# OASIS-Board.net
KiCad netlist of a schematic drawn in EAGLE
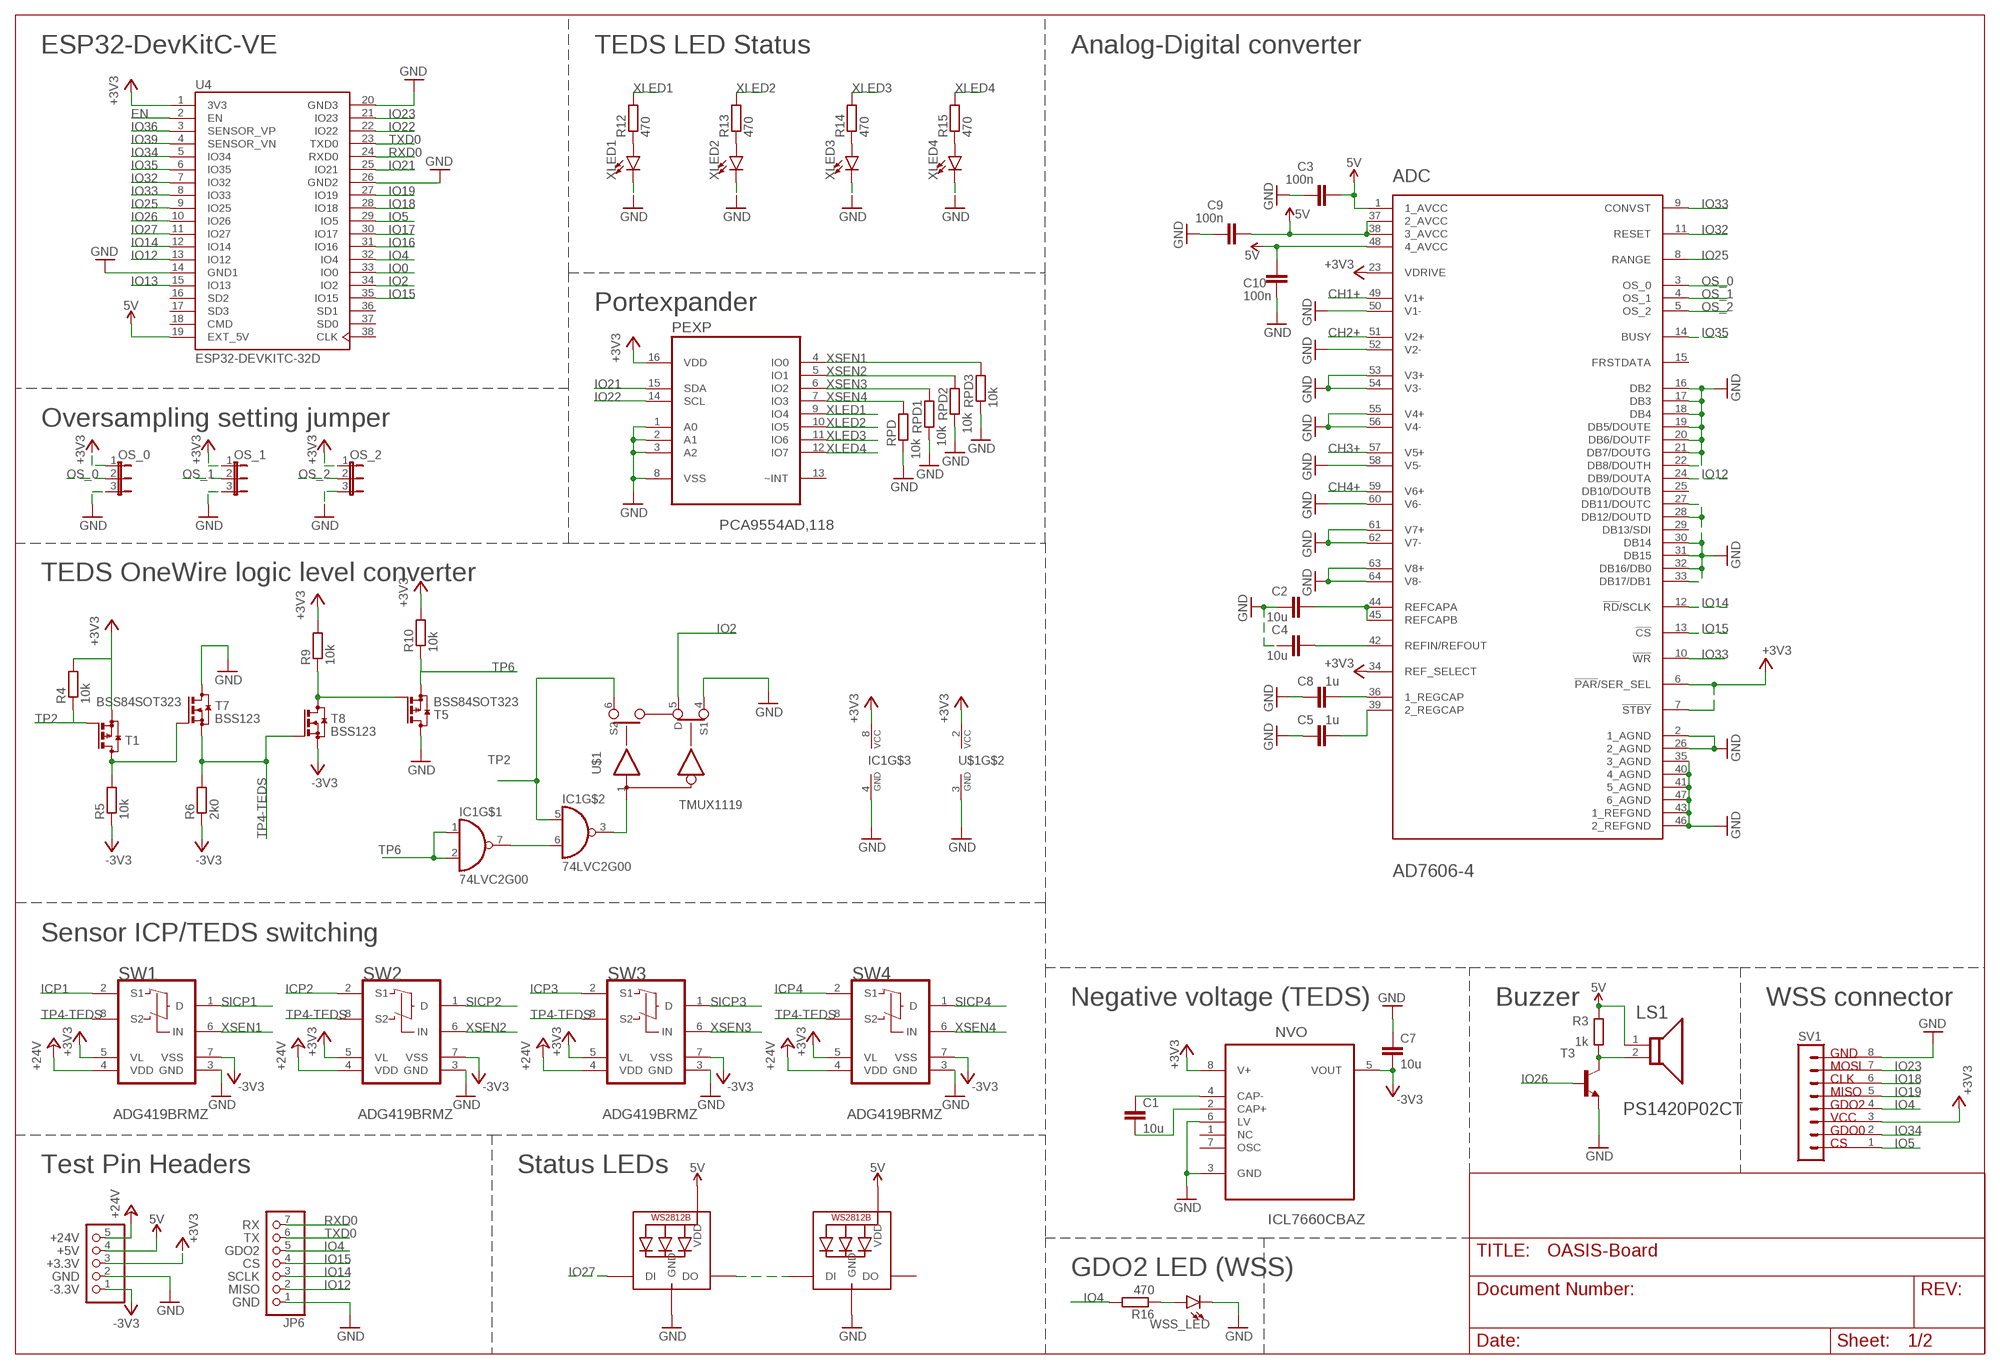
[diagram p0: schematic, sheet 1]
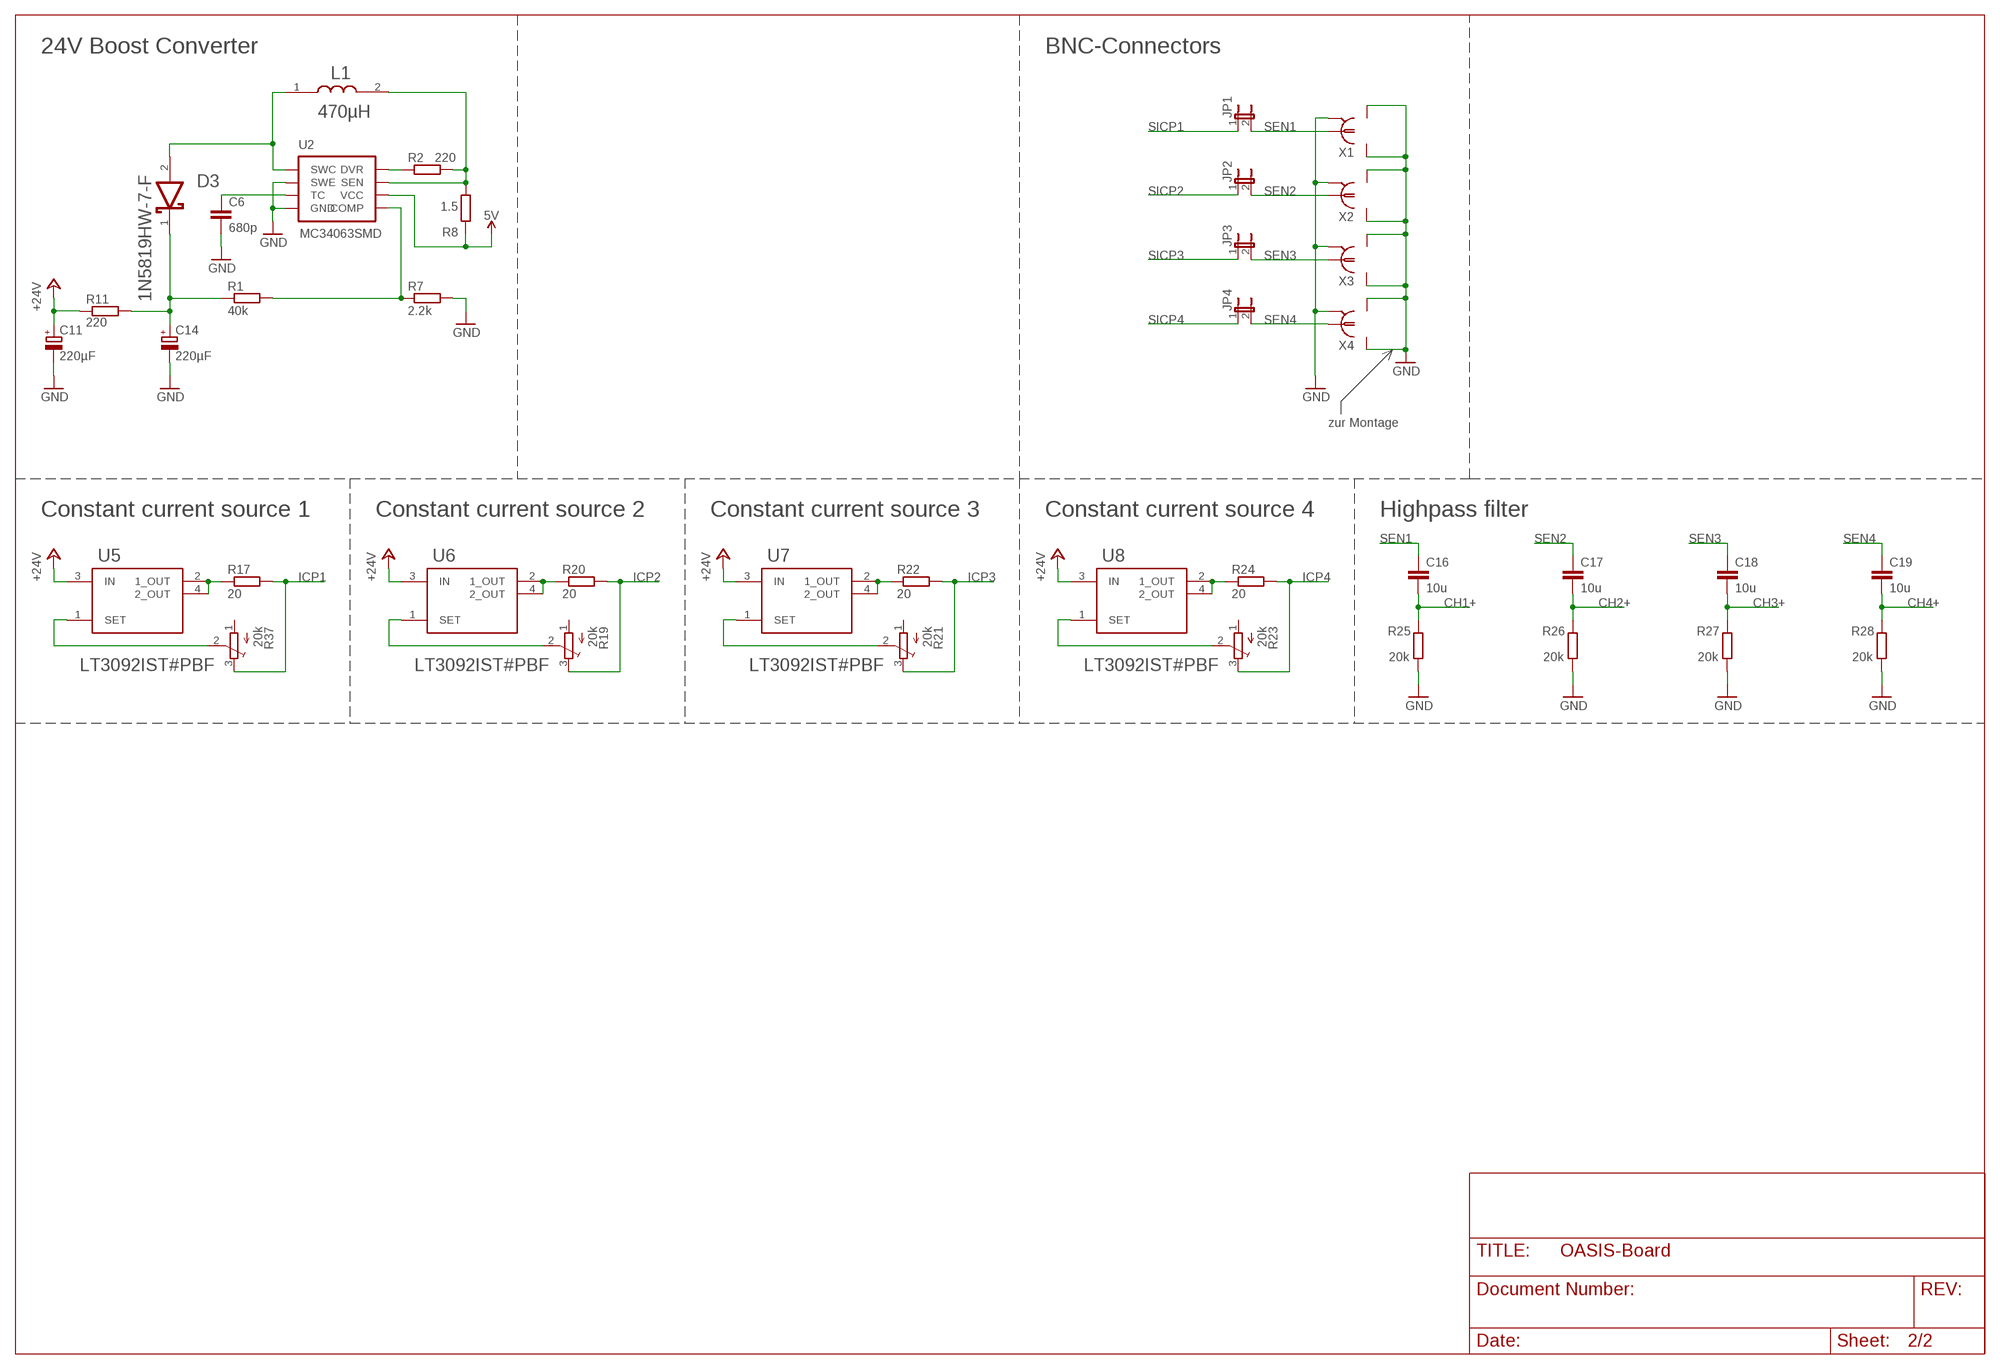
[diagram p1: schematic, sheet 2]

(export (version "E")
  (design (tool "Eeschema 10.0.6"))
  (components
    (comp (ref "ADC")
      (value "ANALOG_DEVICES_AD7606-4ANALOG_DEVICES_AD7606-4_0_0")
      (footprint "eagle-import:ANALOG_DEVICES_AD7606-4_0")
      (fields
        (field (name "DIGIKEY_PART_NUMBER") "505-AD7606-4-ND")
        (field (name "MF") "Analog Devices")
        (field (name "MOUSER_PART_NUMBER") "584-AD7606-4")
      )
      (libsource (lib "eagle-import") (part "ANALOG_DEVICES_AD7606-4ANALOG_DEVICES_AD7606-4_0_0"))
    )
    (comp (ref "C1")
      (value "10u")
      (footprint "eagle-import:C0603")
      (libsource (lib "eagle-import") (part "C-EUC0603"))
    )
    (comp (ref "C2")
      (value "10u")
      (footprint "eagle-import:C0603")
      (libsource (lib "eagle-import") (part "C-EUC0603"))
    )
    (comp (ref "C3")
      (value "100n")
      (footprint "eagle-import:C0603")
      (libsource (lib "eagle-import") (part "C-EUC0603"))
    )
    (comp (ref "C4")
      (value "10u")
      (footprint "eagle-import:C0603")
      (libsource (lib "eagle-import") (part "C-EUC0603"))
    )
    (comp (ref "C5")
      (value "1u")
      (footprint "eagle-import:C0603")
      (libsource (lib "eagle-import") (part "C-EUC0603"))
    )
    (comp (ref "C7")
      (value "10u")
      (footprint "eagle-import:C0603")
      (libsource (lib "eagle-import") (part "C-EUC0603"))
    )
    (comp (ref "C8")
      (value "1u")
      (footprint "eagle-import:C0603")
      (libsource (lib "eagle-import") (part "C-EUC0603"))
    )
    (comp (ref "C9")
      (value "100n")
      (footprint "eagle-import:C0603")
      (libsource (lib "eagle-import") (part "C-EUC0603"))
    )
    (comp (ref "C10")
      (value "100n")
      (footprint "eagle-import:C0603")
      (libsource (lib "eagle-import") (part "C-EUC0603"))
    )
    (comp (ref "IC1")
      (value "74LVC2G00")
      (footprint "eagle-import:TEXAS_INSTRUMENTS_SN74LVC2G00DCUT_2")
      (libsource (lib "eagle-import") (part "74LVC2G00"))
    )
    (comp (ref "JP5")
      (value "PINHD-1X5")
      (footprint "eagle-import:1X05")
      (libsource (lib "eagle-import") (part "PINHD-1X5"))
    )
    (comp (ref "JP6")
      (value "PINHD-1X7")
      (footprint "eagle-import:1X07")
      (libsource (lib "eagle-import") (part "PINHD-1X7"))
    )
    (comp (ref "LS1")
      (value "TDK_PS1420P02CTTDK_PS1420P02CT_0_0")
      (footprint "eagle-import:TDK_PS1420P02CT_0")
      (fields
        (field (name "DIGIKEY_PART_NUMBER") "445-2526-1-ND")
        (field (name "MF") "TDK")
        (field (name "MOUSER_PART_NUMBER") "810-PS1420P02CT")
      )
      (libsource (lib "eagle-import") (part "TDK_PS1420P02CTTDK_PS1420P02CT_0_0"))
    )
    (comp (ref "NVO")
      (value "ICL7660CBAZ")
      (footprint "eagle-import:SOIC127P600X175-8N")
      (fields (field (name "MF") "Renesas Electronics America Inc"))
      (libsource (lib "eagle-import") (part "ICL7660CBAZ"))
    )
    (comp (ref "OS_0")
      (value "JP2E")
      (footprint "eagle-import:JP2")
      (libsource (lib "eagle-import") (part "JP2E"))
    )
    (comp (ref "OS_1")
      (value "JP2E")
      (footprint "eagle-import:JP2")
      (libsource (lib "eagle-import") (part "JP2E"))
    )
    (comp (ref "OS_2")
      (value "JP2E")
      (footprint "eagle-import:JP2")
      (libsource (lib "eagle-import") (part "JP2E"))
    )
    (comp (ref "PEXP")
      (value "PCA9554AD,118")
      (footprint "eagle-import:SOIC127P1032X265-16N")
      (fields (field (name "MF") "NXP Semiconductors"))
      (libsource (lib "eagle-import") (part "PCA9554AD,118"))
    )
    (comp (ref "R3")
      (value "1k")
      (footprint "eagle-import:R0603")
      (libsource (lib "eagle-import") (part "rcl_334_R-EU_R0603"))
    )
    (comp (ref "R4")
      (value "10k")
      (footprint "eagle-import:R0603_MAYR")
      (libsource (lib "eagle-import") (part "R-EU_R0603_MAYR"))
    )
    (comp (ref "R5")
      (value "10k")
      (footprint "eagle-import:R0603_MAYR")
      (libsource (lib "eagle-import") (part "R-EU_R0603_MAYR"))
    )
    (comp (ref "R6")
      (value "2k0")
      (footprint "eagle-import:R0603_MAYR")
      (libsource (lib "eagle-import") (part "R-EU_R0603_MAYR"))
    )
    (comp (ref "R9")
      (value "10k")
      (footprint "eagle-import:R0603_MAYR")
      (libsource (lib "eagle-import") (part "R-EU_R0603_MAYR"))
    )
    (comp (ref "R10")
      (value "10k")
      (footprint "eagle-import:R0603_MAYR")
      (libsource (lib "eagle-import") (part "R-EU_R0603_MAYR"))
    )
    (comp (ref "R12")
      (value "470")
      (footprint "eagle-import:R0603")
      (libsource (lib "eagle-import") (part "rcl_334_R-EU_R0603"))
    )
    (comp (ref "R13")
      (value "470")
      (footprint "eagle-import:R0603")
      (libsource (lib "eagle-import") (part "rcl_334_R-EU_R0603"))
    )
    (comp (ref "R14")
      (value "470")
      (footprint "eagle-import:R0603")
      (libsource (lib "eagle-import") (part "rcl_334_R-EU_R0603"))
    )
    (comp (ref "R15")
      (value "470")
      (footprint "eagle-import:R0603")
      (libsource (lib "eagle-import") (part "rcl_334_R-EU_R0603"))
    )
    (comp (ref "R16")
      (value "470")
      (footprint "eagle-import:R0603")
      (libsource (lib "eagle-import") (part "rcl_334_R-EU_R0603"))
    )
    (comp (ref "RPD")
      (value "10k")
      (footprint "eagle-import:R0603")
      (libsource (lib "eagle-import") (part "rcl_334_R-EU_R0603"))
    )
    (comp (ref "RPD1")
      (value "10k")
      (footprint "eagle-import:R0603")
      (libsource (lib "eagle-import") (part "rcl_334_R-EU_R0603"))
    )
    (comp (ref "RPD2")
      (value "10k")
      (footprint "eagle-import:R0603")
      (libsource (lib "eagle-import") (part "rcl_334_R-EU_R0603"))
    )
    (comp (ref "RPD3")
      (value "10k")
      (footprint "eagle-import:R0603")
      (libsource (lib "eagle-import") (part "rcl_334_R-EU_R0603"))
    )
    (comp (ref "STATUS")
      (value "WS2812B5050")
      (footprint "eagle-import:WS2812B")
      (fields (field (name "MF") "Worldsemi") (field (name "MP") "WS2812B"))
      (libsource (lib "eagle-import") (part "WS2812B5050"))
    )
    (comp (ref "SV1")
      (value "MA08-1")
      (footprint "eagle-import:MA08-1")
      (libsource (lib "eagle-import") (part "MA08-1"))
    )
    (comp (ref "SW1")
      (value "ANALOG_DEVICES_ADG419BRMZANALOG_DEVICES_ADG419BRMZ_0_0")
      (footprint "eagle-import:ANALOG_DEVICES_ADG419BRMZ_0")
      (fields (field (name "MF") "Analog Devices") (field (name "MPN") "ADG419BRMZ"))
      (libsource (lib "eagle-import") (part "ANALOG_DEVICES_ADG419BRMZANALOG_DEVICES_ADG419BRMZ_0_0"))
    )
    (comp (ref "SW2")
      (value "ANALOG_DEVICES_ADG419BRMZANALOG_DEVICES_ADG419BRMZ_0_0")
      (footprint "eagle-import:ANALOG_DEVICES_ADG419BRMZ_0")
      (fields (field (name "MF") "Analog Devices") (field (name "MPN") "ADG419BRMZ"))
      (libsource (lib "eagle-import") (part "ANALOG_DEVICES_ADG419BRMZANALOG_DEVICES_ADG419BRMZ_0_0"))
    )
    (comp (ref "SW3")
      (value "ANALOG_DEVICES_ADG419BRMZANALOG_DEVICES_ADG419BRMZ_0_0")
      (footprint "eagle-import:ANALOG_DEVICES_ADG419BRMZ_0")
      (fields (field (name "MF") "Analog Devices") (field (name "MPN") "ADG419BRMZ"))
      (libsource (lib "eagle-import") (part "ANALOG_DEVICES_ADG419BRMZANALOG_DEVICES_ADG419BRMZ_0_0"))
    )
    (comp (ref "SW4")
      (value "ANALOG_DEVICES_ADG419BRMZANALOG_DEVICES_ADG419BRMZ_0_0")
      (footprint "eagle-import:ANALOG_DEVICES_ADG419BRMZ_0")
      (fields (field (name "MF") "Analog Devices") (field (name "MPN") "ADG419BRMZ"))
      (libsource (lib "eagle-import") (part "ANALOG_DEVICES_ADG419BRMZANALOG_DEVICES_ADG419BRMZ_0_0"))
    )
    (comp (ref "T1")
      (value "BSS84SOT323")
      (footprint "eagle-import:SOT323")
      (libsource (lib "eagle-import") (part "BSS84SOT323"))
    )
    (comp (ref "T3")
      (value "BCF32-NPN-SOT23-BEC")
      (footprint "eagle-import:SOT23-BEC")
      (libsource (lib "eagle-import") (part "-NPN-SOT23-BECBCF32"))
    )
    (comp (ref "T5")
      (value "BSS84SOT323")
      (footprint "eagle-import:SOT323")
      (libsource (lib "eagle-import") (part "BSS84SOT323"))
    )
    (comp (ref "T7")
      (value "BSS123")
      (footprint "eagle-import:SOT23")
      (libsource (lib "eagle-import") (part "BSS123"))
    )
    (comp (ref "T8")
      (value "BSS123")
      (footprint "eagle-import:SOT23")
      (libsource (lib "eagle-import") (part "BSS123"))
    )
    (comp (ref "U$1")
      (value "TMUX1119")
      (footprint "eagle-import:TEXAS_INSTRUMENTS_TMUX1119DCKR_3")
      (libsource (lib "eagle-import") (part "TMUX1119"))
    )
    (comp (ref "U4")
      (value "ESP32-DEVKITC-32D")
      (footprint "eagle-import:MODULE_ESP32-DEVKITC-32D")
      (fields (field (name "MF") "Espressif Systems"))
      (libsource (lib "eagle-import") (part "ESP32-DEVKITC-32D"))
    )
    (comp (ref "WLAN")
      (value "WS2812B5050")
      (footprint "eagle-import:WS2812B")
      (fields (field (name "MF") "Worldsemi") (field (name "MP") "WS2812B"))
      (libsource (lib "eagle-import") (part "WS2812B5050"))
    )
    (comp (ref "WSS_LED")
      (value "LED0603")
      (footprint "eagle-import:LED-0603")
      (libsource (lib "eagle-import") (part "LED0603"))
    )
    (comp (ref "XLED1")
      (value "LED0603")
      (footprint "eagle-import:LED-0603")
      (libsource (lib "eagle-import") (part "LED0603"))
    )
    (comp (ref "XLED2")
      (value "LED0603")
      (footprint "eagle-import:LED-0603")
      (libsource (lib "eagle-import") (part "LED0603"))
    )
    (comp (ref "XLED3")
      (value "LED0603")
      (footprint "eagle-import:LED-0603")
      (libsource (lib "eagle-import") (part "LED0603"))
    )
    (comp (ref "XLED4")
      (value "LED0603")
      (footprint "eagle-import:LED-0603")
      (libsource (lib "eagle-import") (part "LED0603"))
    )
    (comp (ref "C6")
      (value "680p")
      (footprint "eagle-import:C0603")
      (libsource (lib "eagle-import") (part "C-EUC0603"))
    )
    (comp (ref "C11")
      (value "220µF")
      (footprint "eagle-import:153CLV-1012")
      (libsource (lib "eagle-import") (part "CPOL-EU153CLV-1012"))
    )
    (comp (ref "C14")
      (value "220µF")
      (footprint "eagle-import:153CLV-1012")
      (libsource (lib "eagle-import") (part "CPOL-EU153CLV-1012"))
    )
    (comp (ref "C16")
      (value "10u")
      (footprint "eagle-import:C0603")
      (libsource (lib "eagle-import") (part "C-EUC0603"))
    )
    (comp (ref "C17")
      (value "10u")
      (footprint "eagle-import:C0603")
      (libsource (lib "eagle-import") (part "C-EUC0603"))
    )
    (comp (ref "C18")
      (value "10u")
      (footprint "eagle-import:C0603")
      (libsource (lib "eagle-import") (part "C-EUC0603"))
    )
    (comp (ref "C19")
      (value "10u")
      (footprint "eagle-import:C0603")
      (libsource (lib "eagle-import") (part "C-EUC0603"))
    )
    (comp (ref "D3")
      (value "DIODES_1N5819HW-7-FDIODES_1N5819HW-7-F_0_1")
      (footprint "eagle-import:DIODES_1N5819HW-7-F_1")
      (fields
        (field (name "DIGIKEY_PART_NUMBER") "1N5819HW-FDICT-ND")
        (field (name "MF") "Diodes")
        (field (name "MOUSER_PART_NUMBER") "621-1N5819HW-F")
      )
      (libsource (lib "eagle-import") (part "DIODES_1N5819HW-7-FDIODES_1N5819HW-7-F_0_1"))
    )
    (comp (ref "JP1")
      (value "JP1E")
      (footprint "eagle-import:JP1")
      (libsource (lib "eagle-import") (part "JP1E"))
    )
    (comp (ref "JP2")
      (value "JP1E")
      (footprint "eagle-import:JP1")
      (libsource (lib "eagle-import") (part "JP1E"))
    )
    (comp (ref "JP3")
      (value "JP1E")
      (footprint "eagle-import:JP1")
      (libsource (lib "eagle-import") (part "JP1E"))
    )
    (comp (ref "JP4")
      (value "JP1E")
      (footprint "eagle-import:JP1")
      (libsource (lib "eagle-import") (part "JP1E"))
    )
    (comp (ref "L1")
      (value "BOURNS_SRR1260-470MBOURNS_SRR1260-470M_0_0")
      (footprint "eagle-import:BOURNS_SRR1260-470M_0")
      (fields
        (field (name "DIGIKEY_PART_NUMBER") "SRR1260-470MCT-ND")
        (field (name "MF") "Bourns")
        (field (name "MOUSER_PART_NUMBER") "652-SRR1260-470M")
      )
      (libsource (lib "eagle-import") (part "BOURNS_SRR1260-470MBOURNS_SRR1260-470M_0_0"))
    )
    (comp (ref "R1")
      (value "40k")
      (footprint "eagle-import:R0603")
      (libsource (lib "eagle-import") (part "rcl_334_R-EU_R0603"))
    )
    (comp (ref "R2")
      (value "220")
      (footprint "eagle-import:R0603")
      (libsource (lib "eagle-import") (part "rcl_334_R-EU_R0603"))
    )
    (comp (ref "R7")
      (value "2.2k")
      (footprint "eagle-import:R0603")
      (libsource (lib "eagle-import") (part "rcl_334_R-EU_R0603"))
    )
    (comp (ref "R8")
      (value "1.5")
      (footprint "eagle-import:R0603")
      (libsource (lib "eagle-import") (part "rcl_334_R-EU_R0603"))
    )
    (comp (ref "R11")
      (value "220")
      (footprint "eagle-import:R0603")
      (libsource (lib "eagle-import") (part "rcl_334_R-EU_R0603"))
    )
    (comp (ref "R17")
      (value "20")
      (footprint "eagle-import:R0603")
      (libsource (lib "eagle-import") (part "rcl_334_R-EU_R0603"))
    )
    (comp (ref "R19")
      (value "20k")
      (footprint "eagle-import:SM-42_43W")
      (libsource (lib "eagle-import") (part "TRIM_EU-SM-42/43W"))
    )
    (comp (ref "R20")
      (value "20")
      (footprint "eagle-import:R0603")
      (libsource (lib "eagle-import") (part "rcl_334_R-EU_R0603"))
    )
    (comp (ref "R21")
      (value "20k")
      (footprint "eagle-import:SM-42_43W")
      (libsource (lib "eagle-import") (part "TRIM_EU-SM-42/43W"))
    )
    (comp (ref "R22")
      (value "20")
      (footprint "eagle-import:R0603")
      (libsource (lib "eagle-import") (part "rcl_334_R-EU_R0603"))
    )
    (comp (ref "R23")
      (value "20k")
      (footprint "eagle-import:SM-42_43W")
      (libsource (lib "eagle-import") (part "TRIM_EU-SM-42/43W"))
    )
    (comp (ref "R24")
      (value "20")
      (footprint "eagle-import:R0603")
      (libsource (lib "eagle-import") (part "rcl_334_R-EU_R0603"))
    )
    (comp (ref "R25")
      (value "20k")
      (footprint "eagle-import:R0603")
      (libsource (lib "eagle-import") (part "rcl_334_R-EU_R0603"))
    )
    (comp (ref "R26")
      (value "20k")
      (footprint "eagle-import:R0603")
      (libsource (lib "eagle-import") (part "rcl_334_R-EU_R0603"))
    )
    (comp (ref "R27")
      (value "20k")
      (footprint "eagle-import:R0603")
      (libsource (lib "eagle-import") (part "rcl_334_R-EU_R0603"))
    )
    (comp (ref "R28")
      (value "20k")
      (footprint "eagle-import:R0603")
      (libsource (lib "eagle-import") (part "rcl_334_R-EU_R0603"))
    )
    (comp (ref "R37")
      (value "20k")
      (footprint "eagle-import:SM-42_43W")
      (libsource (lib "eagle-import") (part "TRIM_EU-SM-42/43W"))
    )
    (comp (ref "U2")
      (value "MC34063SMD")
      (footprint "eagle-import:SO08")
      (libsource (lib "eagle-import") (part "MC34063SMD"))
    )
    (comp (ref "U5")
      (value "ANALOG_DEVICES_INC_LT3092IST#PBFANALOG_DEVICES_INC_LT3092IST#PBF_0_0")
      (footprint "eagle-import:ANALOG_DEVICES_INC_LT3092IST#PBF_0")
      (fields
        (field (name "DIGIKEY_PART_NUMBER") "LT3092IST#PBF-ND")
        (field (name "MF") "Analog Devices Inc")
        (field (name "MOUSER_PART_NUMBER") "584-LT3092IST#PBF")
      )
      (libsource (lib "eagle-import") (part "ANALOG_DEVICES_INC_LT3092IST#PBFANALOG_DEVICES_INC_LT3092IST#PBF_0_0"))
    )
    (comp (ref "U6")
      (value "ANALOG_DEVICES_INC_LT3092IST#PBFANALOG_DEVICES_INC_LT3092IST#PBF_0_0")
      (footprint "eagle-import:ANALOG_DEVICES_INC_LT3092IST#PBF_0")
      (fields
        (field (name "DIGIKEY_PART_NUMBER") "LT3092IST#PBF-ND")
        (field (name "MF") "Analog Devices Inc")
        (field (name "MOUSER_PART_NUMBER") "584-LT3092IST#PBF")
      )
      (libsource (lib "eagle-import") (part "ANALOG_DEVICES_INC_LT3092IST#PBFANALOG_DEVICES_INC_LT3092IST#PBF_0_0"))
    )
    (comp (ref "U7")
      (value "ANALOG_DEVICES_INC_LT3092IST#PBFANALOG_DEVICES_INC_LT3092IST#PBF_0_0")
      (footprint "eagle-import:ANALOG_DEVICES_INC_LT3092IST#PBF_0")
      (fields
        (field (name "DIGIKEY_PART_NUMBER") "LT3092IST#PBF-ND")
        (field (name "MF") "Analog Devices Inc")
        (field (name "MOUSER_PART_NUMBER") "584-LT3092IST#PBF")
      )
      (libsource (lib "eagle-import") (part "ANALOG_DEVICES_INC_LT3092IST#PBFANALOG_DEVICES_INC_LT3092IST#PBF_0_0"))
    )
    (comp (ref "U8")
      (value "ANALOG_DEVICES_INC_LT3092IST#PBFANALOG_DEVICES_INC_LT3092IST#PBF_0_0")
      (footprint "eagle-import:ANALOG_DEVICES_INC_LT3092IST#PBF_0")
      (fields
        (field (name "DIGIKEY_PART_NUMBER") "LT3092IST#PBF-ND")
        (field (name "MF") "Analog Devices Inc")
        (field (name "MOUSER_PART_NUMBER") "584-LT3092IST#PBF")
      )
      (libsource (lib "eagle-import") (part "ANALOG_DEVICES_INC_LT3092IST#PBFANALOG_DEVICES_INC_LT3092IST#PBF_0_0"))
    )
    (comp (ref "X1")
      (value "BNC")
      (footprint "eagle-import:AMP_227161")
      (libsource (lib "eagle-import") (part "BNC"))
    )
    (comp (ref "X2")
      (value "BNC")
      (footprint "eagle-import:AMP_227161")
      (libsource (lib "eagle-import") (part "BNC"))
    )
    (comp (ref "X3")
      (value "BNC")
      (footprint "eagle-import:AMP_227161")
      (libsource (lib "eagle-import") (part "BNC"))
    )
    (comp (ref "X4")
      (value "BNC")
      (footprint "eagle-import:AMP_227161")
      (libsource (lib "eagle-import") (part "BNC"))
    )
  )
  (nets
    (net (code "1") (name "+3V3") (class "Default")
      (node (ref "ADC") (pin "23") (pinfunction "VDRIVE_23") (pintype "power_in"))
      (node (ref "ADC") (pin "34") (pinfunction "REF_SELECT_34") (pintype "input"))
      (node (ref "ADC") (pin "6") (pinfunction "~{PAR}/SER_SEL_6") (pintype "input"))
      (node (ref "ADC") (pin "7") (pinfunction "~{STBY}_7") (pintype "input"))
      (node (ref "IC1") (pin "8") (pinfunction "VCC_8") (pintype "power_in"))
      (node (ref "JP5") (pin "3") (pinfunction "3_3") (pintype "passive"))
      (node (ref "NVO") (pin "8") (pinfunction "V+_8") (pintype "power_in"))
      (node (ref "OS_0") (pin "1") (pinfunction "1_1") (pintype "passive"))
      (node (ref "OS_1") (pin "1") (pinfunction "1_1") (pintype "passive"))
      (node (ref "OS_2") (pin "1") (pinfunction "1_1") (pintype "passive"))
      (node (ref "PEXP") (pin "16") (pinfunction "VDD_16") (pintype "power_in"))
      (node (ref "R10") (pin "2") (pinfunction "2_2") (pintype "passive"))
      (node (ref "R4") (pin "2") (pinfunction "2_2") (pintype "passive"))
      (node (ref "R9") (pin "2") (pinfunction "2_2") (pintype "passive"))
      (node (ref "SV1") (pin "3") (pinfunction "3_3") (pintype "passive"))
      (node (ref "SW1") (pin "5") (pinfunction "VL_5") (pintype "power_in"))
      (node (ref "SW2") (pin "5") (pinfunction "VL_5") (pintype "power_in"))
      (node (ref "SW3") (pin "5") (pinfunction "VL_5") (pintype "power_in"))
      (node (ref "SW4") (pin "5") (pinfunction "VL_5") (pintype "power_in"))
      (node (ref "T1") (pin "3") (pinfunction "S_3") (pintype "passive"))
      (node (ref "U$1") (pin "2") (pinfunction "VCC_2") (pintype "power_in"))
      (node (ref "U4") (pin "1") (pinfunction "3V3_1") (pintype "power_in"))
    )
    (net (code "2") (name "+24V") (class "Default")
      (node (ref "C11") (pin "+") (pinfunction "+_+") (pintype "passive"))
      (node (ref "JP5") (pin "5") (pinfunction "5_5") (pintype "passive"))
      (node (ref "R11") (pin "1") (pinfunction "1_1") (pintype "passive"))
      (node (ref "SW1") (pin "4") (pinfunction "VDD_4") (pintype "power_in"))
      (node (ref "SW2") (pin "4") (pinfunction "VDD_4") (pintype "power_in"))
      (node (ref "SW3") (pin "4") (pinfunction "VDD_4") (pintype "power_in"))
      (node (ref "SW4") (pin "4") (pinfunction "VDD_4") (pintype "power_in"))
      (node (ref "U5") (pin "3") (pinfunction "IN_3") (pintype "input"))
      (node (ref "U6") (pin "3") (pinfunction "IN_3") (pintype "input"))
      (node (ref "U7") (pin "3") (pinfunction "IN_3") (pintype "input"))
      (node (ref "U8") (pin "3") (pinfunction "IN_3") (pintype "input"))
    )
    (net (code "3") (name "5V") (class "Default")
      (node (ref "ADC") (pin "1") (pinfunction "1_AVCC_1") (pintype "power_in"))
      (node (ref "ADC") (pin "37") (pinfunction "2_AVCC_37") (pintype "power_in"))
      (node (ref "ADC") (pin "38") (pinfunction "3_AVCC_38") (pintype "power_in"))
      (node (ref "ADC") (pin "48") (pinfunction "4_AVCC_48") (pintype "power_in"))
      (node (ref "C10") (pin "2") (pinfunction "2_2") (pintype "passive"))
      (node (ref "C3") (pin "2") (pinfunction "2_2") (pintype "passive"))
      (node (ref "C9") (pin "2") (pinfunction "2_2") (pintype "passive"))
      (node (ref "JP5") (pin "4") (pinfunction "4_4") (pintype "passive"))
      (node (ref "LS1") (pin "1") (pinfunction "1_1") (pintype "bidirectional"))
      (node (ref "R3") (pin "2") (pinfunction "2_2") (pintype "passive"))
      (node (ref "R8") (pin "1") (pinfunction "1_1") (pintype "passive"))
      (node (ref "STATUS") (pin "1-VDD") (pinfunction "VDD_1-VDD") (pintype "power_in"))
      (node (ref "U2") (pin "6") (pinfunction "VCC_6") (pintype "bidirectional"))
      (node (ref "U4") (pin "19") (pinfunction "EXT_5V_19") (pintype "power_in"))
      (node (ref "WLAN") (pin "1-VDD") (pinfunction "VDD_1-VDD") (pintype "power_in"))
    )
    (net (code "4") (name "CH1+") (class "Default")
      (node (ref "ADC") (pin "49") (pinfunction "V1+_49") (pintype "passive"))
      (node (ref "C16") (pin "2") (pinfunction "2_2") (pintype "passive"))
      (node (ref "R25") (pin "2") (pinfunction "2_2") (pintype "passive"))
    )
    (net (code "5") (name "CH2+") (class "Default")
      (node (ref "ADC") (pin "51") (pinfunction "V2+_51") (pintype "passive"))
      (node (ref "C17") (pin "2") (pinfunction "2_2") (pintype "passive"))
      (node (ref "R26") (pin "2") (pinfunction "2_2") (pintype "passive"))
    )
    (net (code "6") (name "CH3+") (class "Default")
      (node (ref "ADC") (pin "57") (pinfunction "V5+_57") (pintype "passive"))
      (node (ref "C18") (pin "2") (pinfunction "2_2") (pintype "passive"))
      (node (ref "R27") (pin "2") (pinfunction "2_2") (pintype "passive"))
    )
    (net (code "7") (name "CH4+") (class "Default")
      (node (ref "ADC") (pin "59") (pinfunction "V6+_59") (pintype "passive"))
      (node (ref "C19") (pin "2") (pinfunction "2_2") (pintype "passive"))
      (node (ref "R28") (pin "2") (pinfunction "2_2") (pintype "passive"))
    )
    (net (code "8") (name "EN") (class "Default")
      (node (ref "U4") (pin "2") (pinfunction "EN_2") (pintype "input"))
    )
    (net (code "9") (name "GND") (class "Default")
      (node (ref "ADC") (pin "16") (pinfunction "DB2_16") (pintype "bidirectional"))
      (node (ref "ADC") (pin "17") (pinfunction "DB3_17") (pintype "bidirectional"))
      (node (ref "ADC") (pin "18") (pinfunction "DB4_18") (pintype "bidirectional"))
      (node (ref "ADC") (pin "19") (pinfunction "DB5/DOUTE_19") (pintype "bidirectional"))
      (node (ref "ADC") (pin "2") (pinfunction "1_AGND_2") (pintype "power_in"))
      (node (ref "ADC") (pin "20") (pinfunction "DB6/DOUTF_20") (pintype "bidirectional"))
      (node (ref "ADC") (pin "21") (pinfunction "DB7/DOUTG_21") (pintype "bidirectional"))
      (node (ref "ADC") (pin "22") (pinfunction "DB8/DOUTH_22") (pintype "bidirectional"))
      (node (ref "ADC") (pin "26") (pinfunction "2_AGND_26") (pintype "power_in"))
      (node (ref "ADC") (pin "27") (pinfunction "DB11/DOUTC_27") (pintype "bidirectional"))
      (node (ref "ADC") (pin "28") (pinfunction "DB12/DOUTD_28") (pintype "bidirectional"))
      (node (ref "ADC") (pin "30") (pinfunction "DB14_30") (pintype "bidirectional"))
      (node (ref "ADC") (pin "31") (pinfunction "DB15_31") (pintype "bidirectional"))
      (node (ref "ADC") (pin "32") (pinfunction "DB16/DB0_32") (pintype "bidirectional"))
      (node (ref "ADC") (pin "33") (pinfunction "DB17/DB1_33") (pintype "bidirectional"))
      (node (ref "ADC") (pin "35") (pinfunction "3_AGND_35") (pintype "power_in"))
      (node (ref "ADC") (pin "40") (pinfunction "4_AGND_40") (pintype "power_in"))
      (node (ref "ADC") (pin "41") (pinfunction "5_AGND_41") (pintype "power_in"))
      (node (ref "ADC") (pin "43") (pinfunction "1_REFGND_43") (pintype "power_in"))
      (node (ref "ADC") (pin "46") (pinfunction "2_REFGND_46") (pintype "power_in"))
      (node (ref "ADC") (pin "47") (pinfunction "6_AGND_47") (pintype "power_in"))
      (node (ref "ADC") (pin "50") (pinfunction "V1-_50") (pintype "passive"))
      (node (ref "ADC") (pin "52") (pinfunction "V2-_52") (pintype "passive"))
      (node (ref "ADC") (pin "53") (pinfunction "V3+_53") (pintype "passive"))
      (node (ref "ADC") (pin "54") (pinfunction "V3-_54") (pintype "passive"))
      (node (ref "ADC") (pin "55") (pinfunction "V4+_55") (pintype "passive"))
      (node (ref "ADC") (pin "56") (pinfunction "V4-_56") (pintype "passive"))
      (node (ref "ADC") (pin "58") (pinfunction "V5-_58") (pintype "passive"))
      (node (ref "ADC") (pin "60") (pinfunction "V6-_60") (pintype "passive"))
      (node (ref "ADC") (pin "61") (pinfunction "V7+_61") (pintype "passive"))
      (node (ref "ADC") (pin "62") (pinfunction "V7-_62") (pintype "passive"))
      (node (ref "ADC") (pin "63") (pinfunction "V8+_63") (pintype "passive"))
      (node (ref "ADC") (pin "64") (pinfunction "V8-_64") (pintype "passive"))
      (node (ref "C10") (pin "1") (pinfunction "1_1") (pintype "passive"))
      (node (ref "C11") (pin "-") (pinfunction "-_-") (pintype "passive"))
      (node (ref "C14") (pin "-") (pinfunction "-_-") (pintype "passive"))
      (node (ref "C2") (pin "1") (pinfunction "1_1") (pintype "passive"))
      (node (ref "C3") (pin "1") (pinfunction "1_1") (pintype "passive"))
      (node (ref "C4") (pin "1") (pinfunction "1_1") (pintype "passive"))
      (node (ref "C5") (pin "1") (pinfunction "1_1") (pintype "passive"))
      (node (ref "C6") (pin "2") (pinfunction "2_2") (pintype "passive"))
      (node (ref "C7") (pin "1") (pinfunction "1_1") (pintype "passive"))
      (node (ref "C8") (pin "1") (pinfunction "1_1") (pintype "passive"))
      (node (ref "C9") (pin "1") (pinfunction "1_1") (pintype "passive"))
      (node (ref "IC1") (pin "4") (pinfunction "GND_4") (pintype "power_in"))
      (node (ref "JP5") (pin "2") (pinfunction "2_2") (pintype "passive"))
      (node (ref "JP6") (pin "1") (pinfunction "1_1") (pintype "passive"))
      (node (ref "NVO") (pin "3") (pinfunction "GND_3") (pintype "passive"))
      (node (ref "NVO") (pin "6") (pinfunction "LV_6") (pintype "input"))
      (node (ref "OS_0") (pin "3") (pinfunction "3_3") (pintype "passive"))
      (node (ref "OS_1") (pin "3") (pinfunction "3_3") (pintype "passive"))
      (node (ref "OS_2") (pin "3") (pinfunction "3_3") (pintype "passive"))
      (node (ref "PEXP") (pin "1") (pinfunction "A0_1") (pintype "input"))
      (node (ref "PEXP") (pin "2") (pinfunction "A1_2") (pintype "input"))
      (node (ref "PEXP") (pin "3") (pinfunction "A2_3") (pintype "input"))
      (node (ref "PEXP") (pin "8") (pinfunction "VSS_8") (pintype "passive"))
      (node (ref "R25") (pin "1") (pinfunction "1_1") (pintype "passive"))
      (node (ref "R26") (pin "1") (pinfunction "1_1") (pintype "passive"))
      (node (ref "R27") (pin "1") (pinfunction "1_1") (pintype "passive"))
      (node (ref "R28") (pin "1") (pinfunction "1_1") (pintype "passive"))
      (node (ref "R7") (pin "2") (pinfunction "2_2") (pintype "passive"))
      (node (ref "RPD") (pin "1") (pinfunction "1_1") (pintype "passive"))
      (node (ref "RPD1") (pin "1") (pinfunction "1_1") (pintype "passive"))
      (node (ref "RPD2") (pin "1") (pinfunction "1_1") (pintype "passive"))
      (node (ref "RPD3") (pin "1") (pinfunction "1_1") (pintype "passive"))
      (node (ref "STATUS") (pin "3-GND") (pinfunction "GND_3-GND") (pintype "power_in"))
      (node (ref "SV1") (pin "8") (pinfunction "8_8") (pintype "passive"))
      (node (ref "SW1") (pin "3") (pinfunction "GND_3") (pintype "power_in"))
      (node (ref "SW2") (pin "3") (pinfunction "GND_3") (pintype "power_in"))
      (node (ref "SW3") (pin "3") (pinfunction "GND_3") (pintype "power_in"))
      (node (ref "SW4") (pin "3") (pinfunction "GND_3") (pintype "power_in"))
      (node (ref "T3") (pin "E") (pinfunction "E_E") (pintype "passive"))
      (node (ref "T5") (pin "1") (pinfunction "D_1") (pintype "passive"))
      (node (ref "T7") (pin "3") (pinfunction "D_3") (pintype "passive"))
      (node (ref "U$1") (pin "3") (pinfunction "GND_3") (pintype "power_in"))
      (node (ref "U$1") (pin "4") (pinfunction "S1_4") (pintype "bidirectional"))
      (node (ref "U2") (pin "2") (pinfunction "SWE_2") (pintype "bidirectional"))
      (node (ref "U2") (pin "4") (pinfunction "GND_4") (pintype "bidirectional"))
      (node (ref "U4") (pin "14") (pinfunction "GND1_14") (pintype "power_in"))
      (node (ref "U4") (pin "20") (pinfunction "GND3_20") (pintype "power_in"))
      (node (ref "U4") (pin "26") (pinfunction "GND2_26") (pintype "power_in"))
      (node (ref "WLAN") (pin "3-GND") (pinfunction "GND_3-GND") (pintype "power_in"))
      (node (ref "WSS_LED") (pin "C") (pinfunction "C_C") (pintype "passive"))
      (node (ref "X1") (pin "2") (pinfunction "2_2") (pintype "passive"))
      (node (ref "X1") (pin "P$1") (pinfunction "P$1_P$1") (pintype "bidirectional"))
      (node (ref "X1") (pin "P$2") (pinfunction "P$2_P$2") (pintype "bidirectional"))
      (node (ref "X2") (pin "2") (pinfunction "2_2") (pintype "passive"))
      (node (ref "X2") (pin "P$1") (pinfunction "P$1_P$1") (pintype "bidirectional"))
      (node (ref "X2") (pin "P$2") (pinfunction "P$2_P$2") (pintype "bidirectional"))
      (node (ref "X3") (pin "2") (pinfunction "2_2") (pintype "passive"))
      (node (ref "X3") (pin "P$1") (pinfunction "P$1_P$1") (pintype "bidirectional"))
      (node (ref "X3") (pin "P$2") (pinfunction "P$2_P$2") (pintype "bidirectional"))
      (node (ref "X4") (pin "2") (pinfunction "2_2") (pintype "passive"))
      (node (ref "X4") (pin "P$1") (pinfunction "P$1_P$1") (pintype "bidirectional"))
      (node (ref "X4") (pin "P$2") (pinfunction "P$2_P$2") (pintype "bidirectional"))
      (node (ref "XLED1") (pin "C") (pinfunction "C_C") (pintype "passive"))
      (node (ref "XLED2") (pin "C") (pinfunction "C_C") (pintype "passive"))
      (node (ref "XLED3") (pin "C") (pinfunction "C_C") (pintype "passive"))
      (node (ref "XLED4") (pin "C") (pinfunction "C_C") (pintype "passive"))
    )
    (net (code "10") (name "ICP1") (class "Default")
      (node (ref "R17") (pin "2") (pinfunction "2_2") (pintype "passive"))
      (node (ref "R37") (pin "3") (pinfunction "E_3") (pintype "passive"))
      (node (ref "SW1") (pin "2") (pinfunction "S1_2") (pintype "passive"))
    )
    (net (code "11") (name "ICP2") (class "Default")
      (node (ref "R19") (pin "3") (pinfunction "E_3") (pintype "passive"))
      (node (ref "R20") (pin "2") (pinfunction "2_2") (pintype "passive"))
      (node (ref "SW2") (pin "2") (pinfunction "S1_2") (pintype "passive"))
    )
    (net (code "12") (name "ICP3") (class "Default")
      (node (ref "R21") (pin "3") (pinfunction "E_3") (pintype "passive"))
      (node (ref "R22") (pin "2") (pinfunction "2_2") (pintype "passive"))
      (node (ref "SW3") (pin "2") (pinfunction "S1_2") (pintype "passive"))
    )
    (net (code "13") (name "ICP4") (class "Default")
      (node (ref "R23") (pin "3") (pinfunction "E_3") (pintype "passive"))
      (node (ref "R24") (pin "2") (pinfunction "2_2") (pintype "passive"))
      (node (ref "SW4") (pin "2") (pinfunction "S1_2") (pintype "passive"))
    )
    (net (code "14") (name "IO0") (class "Default")
      (node (ref "U4") (pin "33") (pinfunction "IO0_33") (pintype "bidirectional"))
    )
    (net (code "15") (name "IO2") (class "Default")
      (node (ref "U$1") (pin "5") (pinfunction "D_5") (pintype "bidirectional"))
      (node (ref "U4") (pin "34") (pinfunction "IO2_34") (pintype "bidirectional"))
    )
    (net (code "16") (name "IO4") (class "Default")
      (node (ref "JP6") (pin "5") (pinfunction "5_5") (pintype "passive"))
      (node (ref "R16") (pin "2") (pinfunction "2_2") (pintype "passive"))
      (node (ref "SV1") (pin "4") (pinfunction "4_4") (pintype "passive"))
      (node (ref "U4") (pin "32") (pinfunction "IO4_32") (pintype "bidirectional"))
    )
    (net (code "17") (name "IO5") (class "Default")
      (node (ref "SV1") (pin "1") (pinfunction "1_1") (pintype "passive"))
      (node (ref "U4") (pin "29") (pinfunction "IO5_29") (pintype "bidirectional"))
    )
    (net (code "18") (name "IO12") (class "Default")
      (node (ref "ADC") (pin "24") (pinfunction "DB9/DOUTA_24") (pintype "bidirectional"))
      (node (ref "JP6") (pin "2") (pinfunction "2_2") (pintype "passive"))
      (node (ref "U4") (pin "13") (pinfunction "IO12_13") (pintype "bidirectional"))
    )
    (net (code "19") (name "IO13") (class "Default")
      (node (ref "U4") (pin "15") (pinfunction "IO13_15") (pintype "bidirectional"))
    )
    (net (code "20") (name "IO14") (class "Default")
      (node (ref "ADC") (pin "12") (pinfunction "~{RD}/SCLK_12") (pintype "input"))
      (node (ref "JP6") (pin "3") (pinfunction "3_3") (pintype "passive"))
      (node (ref "U4") (pin "12") (pinfunction "IO14_12") (pintype "bidirectional"))
    )
    (net (code "21") (name "IO15") (class "Default")
      (node (ref "ADC") (pin "13") (pinfunction "~{CS}_13") (pintype "input"))
      (node (ref "JP6") (pin "4") (pinfunction "4_4") (pintype "passive"))
      (node (ref "U4") (pin "35") (pinfunction "IO15_35") (pintype "bidirectional"))
    )
    (net (code "22") (name "IO16") (class "Default")
      (node (ref "U4") (pin "31") (pinfunction "IO16_31") (pintype "bidirectional"))
    )
    (net (code "23") (name "IO17") (class "Default")
      (node (ref "U4") (pin "30") (pinfunction "IO17_30") (pintype "bidirectional"))
    )
    (net (code "24") (name "IO18") (class "Default")
      (node (ref "SV1") (pin "6") (pinfunction "6_6") (pintype "passive"))
      (node (ref "U4") (pin "28") (pinfunction "IO18_28") (pintype "bidirectional"))
    )
    (net (code "25") (name "IO19") (class "Default")
      (node (ref "SV1") (pin "5") (pinfunction "5_5") (pintype "passive"))
      (node (ref "U4") (pin "27") (pinfunction "IO19_27") (pintype "bidirectional"))
    )
    (net (code "26") (name "IO21") (class "Default")
      (node (ref "PEXP") (pin "15") (pinfunction "SDA_15") (pintype "bidirectional"))
      (node (ref "U4") (pin "25") (pinfunction "IO21_25") (pintype "bidirectional"))
    )
    (net (code "27") (name "IO22") (class "Default")
      (node (ref "PEXP") (pin "14") (pinfunction "SCL_14") (pintype "input"))
      (node (ref "U4") (pin "22") (pinfunction "IO22_22") (pintype "bidirectional"))
    )
    (net (code "28") (name "IO23") (class "Default")
      (node (ref "SV1") (pin "7") (pinfunction "7_7") (pintype "passive"))
      (node (ref "U4") (pin "21") (pinfunction "IO23_21") (pintype "bidirectional"))
    )
    (net (code "29") (name "IO25") (class "Default")
      (node (ref "ADC") (pin "8") (pinfunction "RANGE_8") (pintype "input"))
      (node (ref "U4") (pin "9") (pinfunction "IO25_9") (pintype "bidirectional"))
    )
    (net (code "30") (name "IO26") (class "Default")
      (node (ref "T3") (pin "B") (pinfunction "B_B") (pintype "passive"))
      (node (ref "U4") (pin "10") (pinfunction "IO26_10") (pintype "bidirectional"))
    )
    (net (code "31") (name "IO27") (class "Default")
      (node (ref "STATUS") (pin "4-DIN") (pinfunction "DI_4-DIN") (pintype "input"))
      (node (ref "U4") (pin "11") (pinfunction "IO27_11") (pintype "bidirectional"))
    )
    (net (code "32") (name "IO32") (class "Default")
      (node (ref "ADC") (pin "11") (pinfunction "RESET_11") (pintype "input"))
      (node (ref "U4") (pin "7") (pinfunction "IO32_7") (pintype "bidirectional"))
    )
    (net (code "33") (name "IO33") (class "Default")
      (node (ref "ADC") (pin "10") (pinfunction "~{WR}_10") (pintype "input"))
      (node (ref "ADC") (pin "9") (pinfunction "CONVST_9") (pintype "input"))
      (node (ref "U4") (pin "8") (pinfunction "IO33_8") (pintype "bidirectional"))
    )
    (net (code "34") (name "IO34") (class "Default")
      (node (ref "SV1") (pin "2") (pinfunction "2_2") (pintype "passive"))
      (node (ref "U4") (pin "5") (pinfunction "IO34_5") (pintype "bidirectional"))
    )
    (net (code "35") (name "IO35") (class "Default")
      (node (ref "ADC") (pin "14") (pinfunction "BUSY_14") (pintype "output"))
      (node (ref "U4") (pin "6") (pinfunction "IO35_6") (pintype "bidirectional"))
    )
    (net (code "36") (name "IO36") (class "Default")
      (node (ref "U4") (pin "3") (pinfunction "SENSOR_VP_3") (pintype "input"))
    )
    (net (code "37") (name "IO39") (class "Default")
      (node (ref "U4") (pin "4") (pinfunction "SENSOR_VN_4") (pintype "input"))
    )
    (net (code "38") (name "Net-(ADC-1_REGCAP)") (class "Default")
      (node (ref "ADC") (pin "36") (pinfunction "1_REGCAP_36") (pintype "passive"))
      (node (ref "C8") (pin "2") (pinfunction "2_2") (pintype "passive"))
    )
    (net (code "39") (name "Net-(ADC-2_REGCAP)") (class "Default")
      (node (ref "ADC") (pin "39") (pinfunction "2_REGCAP_39") (pintype "passive"))
      (node (ref "C5") (pin "2") (pinfunction "2_2") (pintype "passive"))
    )
    (net (code "40") (name "Net-(ADC-REFCAPA)") (class "Default")
      (node (ref "ADC") (pin "44") (pinfunction "REFCAPA_44") (pintype "passive"))
      (node (ref "ADC") (pin "45") (pinfunction "REFCAPB_45") (pintype "passive"))
      (node (ref "C2") (pin "2") (pinfunction "2_2") (pintype "passive"))
    )
    (net (code "41") (name "Net-(ADC-REFIN{slash}REFOUT)") (class "Default")
      (node (ref "ADC") (pin "42") (pinfunction "REFIN/REFOUT_42") (pintype "passive"))
      (node (ref "C4") (pin "2") (pinfunction "2_2") (pintype "passive"))
    )
    (net (code "42") (name "Net-(D3-ANODE)") (class "Default")
      (node (ref "D3") (pin "2") (pinfunction "ANODE_2") (pintype "passive"))
      (node (ref "L1") (pin "1") (pinfunction "1_1") (pintype "bidirectional"))
      (node (ref "U2") (pin "1") (pinfunction "SWC_1") (pintype "bidirectional"))
    )
    (net (code "43") (name "Net-(D3-CATHODE)") (class "Default")
      (node (ref "C14") (pin "+") (pinfunction "+_+") (pintype "passive"))
      (node (ref "D3") (pin "1") (pinfunction "CATHODE_1") (pintype "passive"))
      (node (ref "R1") (pin "1") (pinfunction "1_1") (pintype "passive"))
      (node (ref "R11") (pin "2") (pinfunction "2_2") (pintype "passive"))
    )
    (net (code "44") (name "Net-(IC1A-O)") (class "Default")
      (node (ref "IC1") (pin "6") (pinfunction "I1_6") (pintype "input"))
      (node (ref "IC1") (pin "7") (pinfunction "O_7") (pintype "output"))
    )
    (net (code "45") (name "Net-(IC1B-O)") (class "Default")
      (node (ref "IC1") (pin "3") (pinfunction "O_3") (pintype "output"))
      (node (ref "U$1") (pin "1") (pinfunction "IN_1") (pintype "input"))
    )
    (net (code "46") (name "Net-(LS1-Pad2)") (class "Default")
      (node (ref "LS1") (pin "2") (pinfunction "2_2") (pintype "bidirectional"))
      (node (ref "R3") (pin "1") (pinfunction "1_1") (pintype "passive"))
      (node (ref "T3") (pin "C") (pinfunction "C_C") (pintype "passive"))
    )
    (net (code "47") (name "Net-(NVO-CAP+)") (class "Default")
      (node (ref "C1") (pin "2") (pinfunction "2_2") (pintype "passive"))
      (node (ref "NVO") (pin "2") (pinfunction "CAP+_2") (pintype "passive"))
    )
    (net (code "48") (name "Net-(NVO-CAP-)") (class "Default")
      (node (ref "C1") (pin "1") (pinfunction "1_1") (pintype "passive"))
      (node (ref "NVO") (pin "4") (pinfunction "CAP-_4") (pintype "passive"))
    )
    (net (code "49") (name "Net-(R12-Pad1)") (class "Default")
      (node (ref "R12") (pin "1") (pinfunction "1_1") (pintype "passive"))
      (node (ref "XLED1") (pin "A") (pinfunction "A_A") (pintype "passive"))
    )
    (net (code "50") (name "Net-(R13-Pad1)") (class "Default")
      (node (ref "R13") (pin "1") (pinfunction "1_1") (pintype "passive"))
      (node (ref "XLED2") (pin "A") (pinfunction "A_A") (pintype "passive"))
    )
    (net (code "51") (name "Net-(R14-Pad1)") (class "Default")
      (node (ref "R14") (pin "1") (pinfunction "1_1") (pintype "passive"))
      (node (ref "XLED3") (pin "A") (pinfunction "A_A") (pintype "passive"))
    )
    (net (code "52") (name "Net-(R15-Pad1)") (class "Default")
      (node (ref "R15") (pin "1") (pinfunction "1_1") (pintype "passive"))
      (node (ref "XLED4") (pin "A") (pinfunction "A_A") (pintype "passive"))
    )
    (net (code "53") (name "Net-(R16-Pad1)") (class "Default")
      (node (ref "R16") (pin "1") (pinfunction "1_1") (pintype "passive"))
      (node (ref "WSS_LED") (pin "A") (pinfunction "A_A") (pintype "passive"))
    )
    (net (code "54") (name "Net-(R19-S)") (class "Default")
      (node (ref "R19") (pin "2") (pinfunction "S_2") (pintype "passive"))
      (node (ref "U6") (pin "1") (pinfunction "SET_1") (pintype "input"))
    )
    (net (code "55") (name "Net-(R21-S)") (class "Default")
      (node (ref "R21") (pin "2") (pinfunction "S_2") (pintype "passive"))
      (node (ref "U7") (pin "1") (pinfunction "SET_1") (pintype "input"))
    )
    (net (code "56") (name "Net-(R23-S)") (class "Default")
      (node (ref "R23") (pin "2") (pinfunction "S_2") (pintype "passive"))
      (node (ref "U8") (pin "1") (pinfunction "SET_1") (pintype "input"))
    )
    (net (code "57") (name "Net-(R37-S)") (class "Default")
      (node (ref "R37") (pin "2") (pinfunction "S_2") (pintype "passive"))
      (node (ref "U5") (pin "1") (pinfunction "SET_1") (pintype "input"))
    )
    (net (code "58") (name "Net-(STATUS-DO)") (class "Default")
      (node (ref "STATUS") (pin "2-DOUT") (pinfunction "DO_2-DOUT") (pintype "output"))
      (node (ref "WLAN") (pin "4-DIN") (pinfunction "DI_4-DIN") (pintype "input"))
    )
    (net (code "59") (name "Net-(T1-D)") (class "Default")
      (node (ref "R5") (pin "2") (pinfunction "2_2") (pintype "passive"))
      (node (ref "T1") (pin "1") (pinfunction "D_1") (pintype "passive"))
      (node (ref "T7") (pin "1") (pinfunction "G_1") (pintype "passive"))
    )
    (net (code "60") (name "Net-(T5-G)") (class "Default")
      (node (ref "R9") (pin "1") (pinfunction "1_1") (pintype "passive"))
      (node (ref "T5") (pin "2") (pinfunction "G_2") (pintype "passive"))
      (node (ref "T8") (pin "3") (pinfunction "D_3") (pintype "passive"))
    )
    (net (code "61") (name "Net-(U2-COMP)") (class "Default")
      (node (ref "R1") (pin "2") (pinfunction "2_2") (pintype "passive"))
      (node (ref "R7") (pin "1") (pinfunction "1_1") (pintype "passive"))
      (node (ref "U2") (pin "5") (pinfunction "COMP_5") (pintype "bidirectional"))
    )
    (net (code "62") (name "Net-(U2-DVR)") (class "Default")
      (node (ref "R2") (pin "1") (pinfunction "1_1") (pintype "passive"))
      (node (ref "U2") (pin "8") (pinfunction "DVR_8") (pintype "bidirectional"))
    )
    (net (code "63") (name "Net-(U2-SEN)") (class "Default")
      (node (ref "L1") (pin "2") (pinfunction "2_2") (pintype "bidirectional"))
      (node (ref "R2") (pin "2") (pinfunction "2_2") (pintype "passive"))
      (node (ref "R8") (pin "2") (pinfunction "2_2") (pintype "passive"))
      (node (ref "U2") (pin "7") (pinfunction "SEN_7") (pintype "bidirectional"))
    )
    (net (code "64") (name "Net-(U2-TC)") (class "Default")
      (node (ref "C6") (pin "1") (pinfunction "1_1") (pintype "passive"))
      (node (ref "U2") (pin "3") (pinfunction "TC_3") (pintype "bidirectional"))
    )
    (net (code "65") (name "Net-(U5-1_OUT)") (class "Default")
      (node (ref "R17") (pin "1") (pinfunction "1_1") (pintype "passive"))
      (node (ref "U5") (pin "2") (pinfunction "1_OUT_2") (pintype "output"))
      (node (ref "U5") (pin "4") (pinfunction "2_OUT_4") (pintype "output"))
    )
    (net (code "66") (name "Net-(U6-1_OUT)") (class "Default")
      (node (ref "R20") (pin "1") (pinfunction "1_1") (pintype "passive"))
      (node (ref "U6") (pin "2") (pinfunction "1_OUT_2") (pintype "output"))
      (node (ref "U6") (pin "4") (pinfunction "2_OUT_4") (pintype "output"))
    )
    (net (code "67") (name "Net-(U7-1_OUT)") (class "Default")
      (node (ref "R22") (pin "1") (pinfunction "1_1") (pintype "passive"))
      (node (ref "U7") (pin "2") (pinfunction "1_OUT_2") (pintype "output"))
      (node (ref "U7") (pin "4") (pinfunction "2_OUT_4") (pintype "output"))
    )
    (net (code "68") (name "Net-(U8-1_OUT)") (class "Default")
      (node (ref "R24") (pin "1") (pinfunction "1_1") (pintype "passive"))
      (node (ref "U8") (pin "2") (pinfunction "1_OUT_2") (pintype "output"))
      (node (ref "U8") (pin "4") (pinfunction "2_OUT_4") (pintype "output"))
    )
    (net (code "69") (name "OS_0") (class "Default")
      (node (ref "ADC") (pin "3") (pinfunction "OS_0_3") (pintype "passive"))
      (node (ref "OS_0") (pin "2") (pinfunction "2_2") (pintype "passive"))
    )
    (net (code "70") (name "OS_1") (class "Default")
      (node (ref "ADC") (pin "4") (pinfunction "OS_1_4") (pintype "passive"))
      (node (ref "OS_1") (pin "2") (pinfunction "2_2") (pintype "passive"))
    )
    (net (code "71") (name "OS_2") (class "Default")
      (node (ref "ADC") (pin "5") (pinfunction "OS_2_5") (pintype "passive"))
      (node (ref "OS_2") (pin "2") (pinfunction "2_2") (pintype "passive"))
    )
    (net (code "72") (name "RXD0") (class "Default")
      (node (ref "JP6") (pin "7") (pinfunction "7_7") (pintype "passive"))
      (node (ref "U4") (pin "24") (pinfunction "RXD0_24") (pintype "input"))
    )
    (net (code "73") (name "SEN1") (class "Default")
      (node (ref "C16") (pin "1") (pinfunction "1_1") (pintype "passive"))
      (node (ref "JP1") (pin "2") (pinfunction "2_2") (pintype "passive"))
      (node (ref "X1") (pin "1") (pinfunction "1_1") (pintype "passive"))
    )
    (net (code "74") (name "SEN2") (class "Default")
      (node (ref "C17") (pin "1") (pinfunction "1_1") (pintype "passive"))
      (node (ref "JP2") (pin "2") (pinfunction "2_2") (pintype "passive"))
      (node (ref "X2") (pin "1") (pinfunction "1_1") (pintype "passive"))
    )
    (net (code "75") (name "SEN3") (class "Default")
      (node (ref "C18") (pin "1") (pinfunction "1_1") (pintype "passive"))
      (node (ref "JP3") (pin "2") (pinfunction "2_2") (pintype "passive"))
      (node (ref "X3") (pin "1") (pinfunction "1_1") (pintype "passive"))
    )
    (net (code "76") (name "SEN4") (class "Default")
      (node (ref "C19") (pin "1") (pinfunction "1_1") (pintype "passive"))
      (node (ref "JP4") (pin "2") (pinfunction "2_2") (pintype "passive"))
      (node (ref "X4") (pin "1") (pinfunction "1_1") (pintype "passive"))
    )
    (net (code "77") (name "SICP1") (class "Default")
      (node (ref "JP1") (pin "1") (pinfunction "1_1") (pintype "passive"))
      (node (ref "SW1") (pin "1") (pinfunction "D_1") (pintype "passive"))
    )
    (net (code "78") (name "SICP2") (class "Default")
      (node (ref "JP2") (pin "1") (pinfunction "1_1") (pintype "passive"))
      (node (ref "SW2") (pin "1") (pinfunction "D_1") (pintype "passive"))
    )
    (net (code "79") (name "SICP3") (class "Default")
      (node (ref "JP3") (pin "1") (pinfunction "1_1") (pintype "passive"))
      (node (ref "SW3") (pin "1") (pinfunction "D_1") (pintype "passive"))
    )
    (net (code "80") (name "SICP4") (class "Default")
      (node (ref "JP4") (pin "1") (pinfunction "1_1") (pintype "passive"))
      (node (ref "SW4") (pin "1") (pinfunction "D_1") (pintype "passive"))
    )
    (net (code "81") (name "TP2") (class "Default")
      (node (ref "IC1") (pin "5") (pinfunction "I0_5") (pintype "input"))
      (node (ref "R4") (pin "1") (pinfunction "1_1") (pintype "passive"))
      (node (ref "T1") (pin "2") (pinfunction "G_2") (pintype "passive"))
      (node (ref "U$1") (pin "6") (pinfunction "S2_6") (pintype "bidirectional"))
    )
    (net (code "82") (name "TP4-TEDS") (class "Default")
      (node (ref "R6") (pin "2") (pinfunction "2_2") (pintype "passive"))
      (node (ref "SW1") (pin "8") (pinfunction "S2_8") (pintype "passive"))
      (node (ref "SW2") (pin "8") (pinfunction "S2_8") (pintype "passive"))
      (node (ref "SW3") (pin "8") (pinfunction "S2_8") (pintype "passive"))
      (node (ref "SW4") (pin "8") (pinfunction "S2_8") (pintype "passive"))
      (node (ref "T7") (pin "2") (pinfunction "S_2") (pintype "passive"))
      (node (ref "T8") (pin "1") (pinfunction "G_1") (pintype "passive"))
    )
    (net (code "83") (name "TP6") (class "Default")
      (node (ref "IC1") (pin "1") (pinfunction "I0_1") (pintype "input"))
      (node (ref "IC1") (pin "2") (pinfunction "I1_2") (pintype "input"))
      (node (ref "R10") (pin "1") (pinfunction "1_1") (pintype "passive"))
      (node (ref "T5") (pin "3") (pinfunction "S_3") (pintype "passive"))
    )
    (net (code "84") (name "TXD0") (class "Default")
      (node (ref "JP6") (pin "6") (pinfunction "6_6") (pintype "passive"))
      (node (ref "U4") (pin "23") (pinfunction "TXD0_23") (pintype "output"))
    )
    (net (code "85") (name "V-") (class "Default")
      (node (ref "C7") (pin "2") (pinfunction "2_2") (pintype "passive"))
      (node (ref "JP5") (pin "1") (pinfunction "1_1") (pintype "passive"))
      (node (ref "NVO") (pin "5") (pinfunction "VOUT_5") (pintype "output"))
      (node (ref "R5") (pin "1") (pinfunction "1_1") (pintype "passive"))
      (node (ref "R6") (pin "1") (pinfunction "1_1") (pintype "passive"))
      (node (ref "SW1") (pin "7") (pinfunction "VSS_7") (pintype "power_in"))
      (node (ref "SW2") (pin "7") (pinfunction "VSS_7") (pintype "power_in"))
      (node (ref "SW3") (pin "7") (pinfunction "VSS_7") (pintype "power_in"))
      (node (ref "SW4") (pin "7") (pinfunction "VSS_7") (pintype "power_in"))
      (node (ref "T8") (pin "2") (pinfunction "S_2") (pintype "passive"))
    )
    (net (code "86") (name "XLED1") (class "Default")
      (node (ref "PEXP") (pin "9") (pinfunction "IO4_9") (pintype "bidirectional"))
      (node (ref "R12") (pin "2") (pinfunction "2_2") (pintype "passive"))
    )
    (net (code "87") (name "XLED2") (class "Default")
      (node (ref "PEXP") (pin "10") (pinfunction "IO5_10") (pintype "bidirectional"))
      (node (ref "R13") (pin "2") (pinfunction "2_2") (pintype "passive"))
    )
    (net (code "88") (name "XLED3") (class "Default")
      (node (ref "PEXP") (pin "11") (pinfunction "IO6_11") (pintype "bidirectional"))
      (node (ref "R14") (pin "2") (pinfunction "2_2") (pintype "passive"))
    )
    (net (code "89") (name "XLED4") (class "Default")
      (node (ref "PEXP") (pin "12") (pinfunction "IO7_12") (pintype "bidirectional"))
      (node (ref "R15") (pin "2") (pinfunction "2_2") (pintype "passive"))
    )
    (net (code "90") (name "XSEN1") (class "Default")
      (node (ref "PEXP") (pin "4") (pinfunction "IO0_4") (pintype "bidirectional"))
      (node (ref "RPD3") (pin "2") (pinfunction "2_2") (pintype "passive"))
      (node (ref "SW1") (pin "6") (pinfunction "IN_6") (pintype "input"))
    )
    (net (code "91") (name "XSEN2") (class "Default")
      (node (ref "PEXP") (pin "5") (pinfunction "IO1_5") (pintype "bidirectional"))
      (node (ref "RPD2") (pin "2") (pinfunction "2_2") (pintype "passive"))
      (node (ref "SW2") (pin "6") (pinfunction "IN_6") (pintype "input"))
    )
    (net (code "92") (name "XSEN3") (class "Default")
      (node (ref "PEXP") (pin "6") (pinfunction "IO2_6") (pintype "bidirectional"))
      (node (ref "RPD1") (pin "2") (pinfunction "2_2") (pintype "passive"))
      (node (ref "SW3") (pin "6") (pinfunction "IN_6") (pintype "input"))
    )
    (net (code "93") (name "XSEN4") (class "Default")
      (node (ref "PEXP") (pin "7") (pinfunction "IO3_7") (pintype "bidirectional"))
      (node (ref "RPD") (pin "2") (pinfunction "2_2") (pintype "passive"))
      (node (ref "SW4") (pin "6") (pinfunction "IN_6") (pintype "input"))
    )
    (net (code "94") (name "unconnected-(ADC-DB10{slash}DOUTB-Pad25)") (class "Default")
      (node (ref "ADC") (pin "25") (pinfunction "DB10/DOUTB_25") (pintype "bidirectional"))
    )
    (net (code "95") (name "unconnected-(ADC-DB13{slash}SDI-Pad29)") (class "Default")
      (node (ref "ADC") (pin "29") (pinfunction "DB13/SDI_29") (pintype "bidirectional"))
    )
    (net (code "96") (name "unconnected-(ADC-FRSTDATA-Pad15)") (class "Default")
      (node (ref "ADC") (pin "15") (pinfunction "FRSTDATA_15") (pintype "output"))
    )
    (net (code "97") (name "unconnected-(NVO-NC-Pad1)") (class "Default")
      (node (ref "NVO") (pin "1") (pinfunction "NC_1") (pintype "no_connect"))
    )
    (net (code "98") (name "unconnected-(NVO-OSC-Pad7)") (class "Default")
      (node (ref "NVO") (pin "7") (pinfunction "OSC_7") (pintype "input"))
    )
    (net (code "99") (name "unconnected-(PEXP-~{INT}-Pad13)") (class "Default")
      (node (ref "PEXP") (pin "13") (pinfunction "~{INT}_13") (pintype "output"))
    )
    (net (code "100") (name "unconnected-(R19-A-Pad1)") (class "Default")
      (node (ref "R19") (pin "1") (pinfunction "A_1") (pintype "passive"))
    )
    (net (code "101") (name "unconnected-(R21-A-Pad1)") (class "Default")
      (node (ref "R21") (pin "1") (pinfunction "A_1") (pintype "passive"))
    )
    (net (code "102") (name "unconnected-(R23-A-Pad1)") (class "Default")
      (node (ref "R23") (pin "1") (pinfunction "A_1") (pintype "passive"))
    )
    (net (code "103") (name "unconnected-(R37-A-Pad1)") (class "Default")
      (node (ref "R37") (pin "1") (pinfunction "A_1") (pintype "passive"))
    )
    (net (code "104") (name "unconnected-(U4-CLK-Pad38)") (class "Default")
      (node (ref "U4") (pin "38") (pinfunction "CLK_38") (pintype "input"))
    )
    (net (code "105") (name "unconnected-(U4-CMD-Pad18)") (class "Default")
      (node (ref "U4") (pin "18") (pinfunction "CMD_18") (pintype "bidirectional"))
    )
    (net (code "106") (name "unconnected-(U4-SD0-Pad37)") (class "Default")
      (node (ref "U4") (pin "37") (pinfunction "SD0_37") (pintype "bidirectional"))
    )
    (net (code "107") (name "unconnected-(U4-SD1-Pad36)") (class "Default")
      (node (ref "U4") (pin "36") (pinfunction "SD1_36") (pintype "bidirectional"))
    )
    (net (code "108") (name "unconnected-(U4-SD2-Pad16)") (class "Default")
      (node (ref "U4") (pin "16") (pinfunction "SD2_16") (pintype "bidirectional"))
    )
    (net (code "109") (name "unconnected-(U4-SD3-Pad17)") (class "Default")
      (node (ref "U4") (pin "17") (pinfunction "SD3_17") (pintype "bidirectional"))
    )
    (net (code "110") (name "unconnected-(WLAN-DO-Pad2-DOUT)") (class "Default")
      (node (ref "WLAN") (pin "2-DOUT") (pinfunction "DO_2-DOUT") (pintype "output"))
    )
  )
)
